# MFP_Schematic.net
KiCad netlist of a schematic drawn in EAGLE
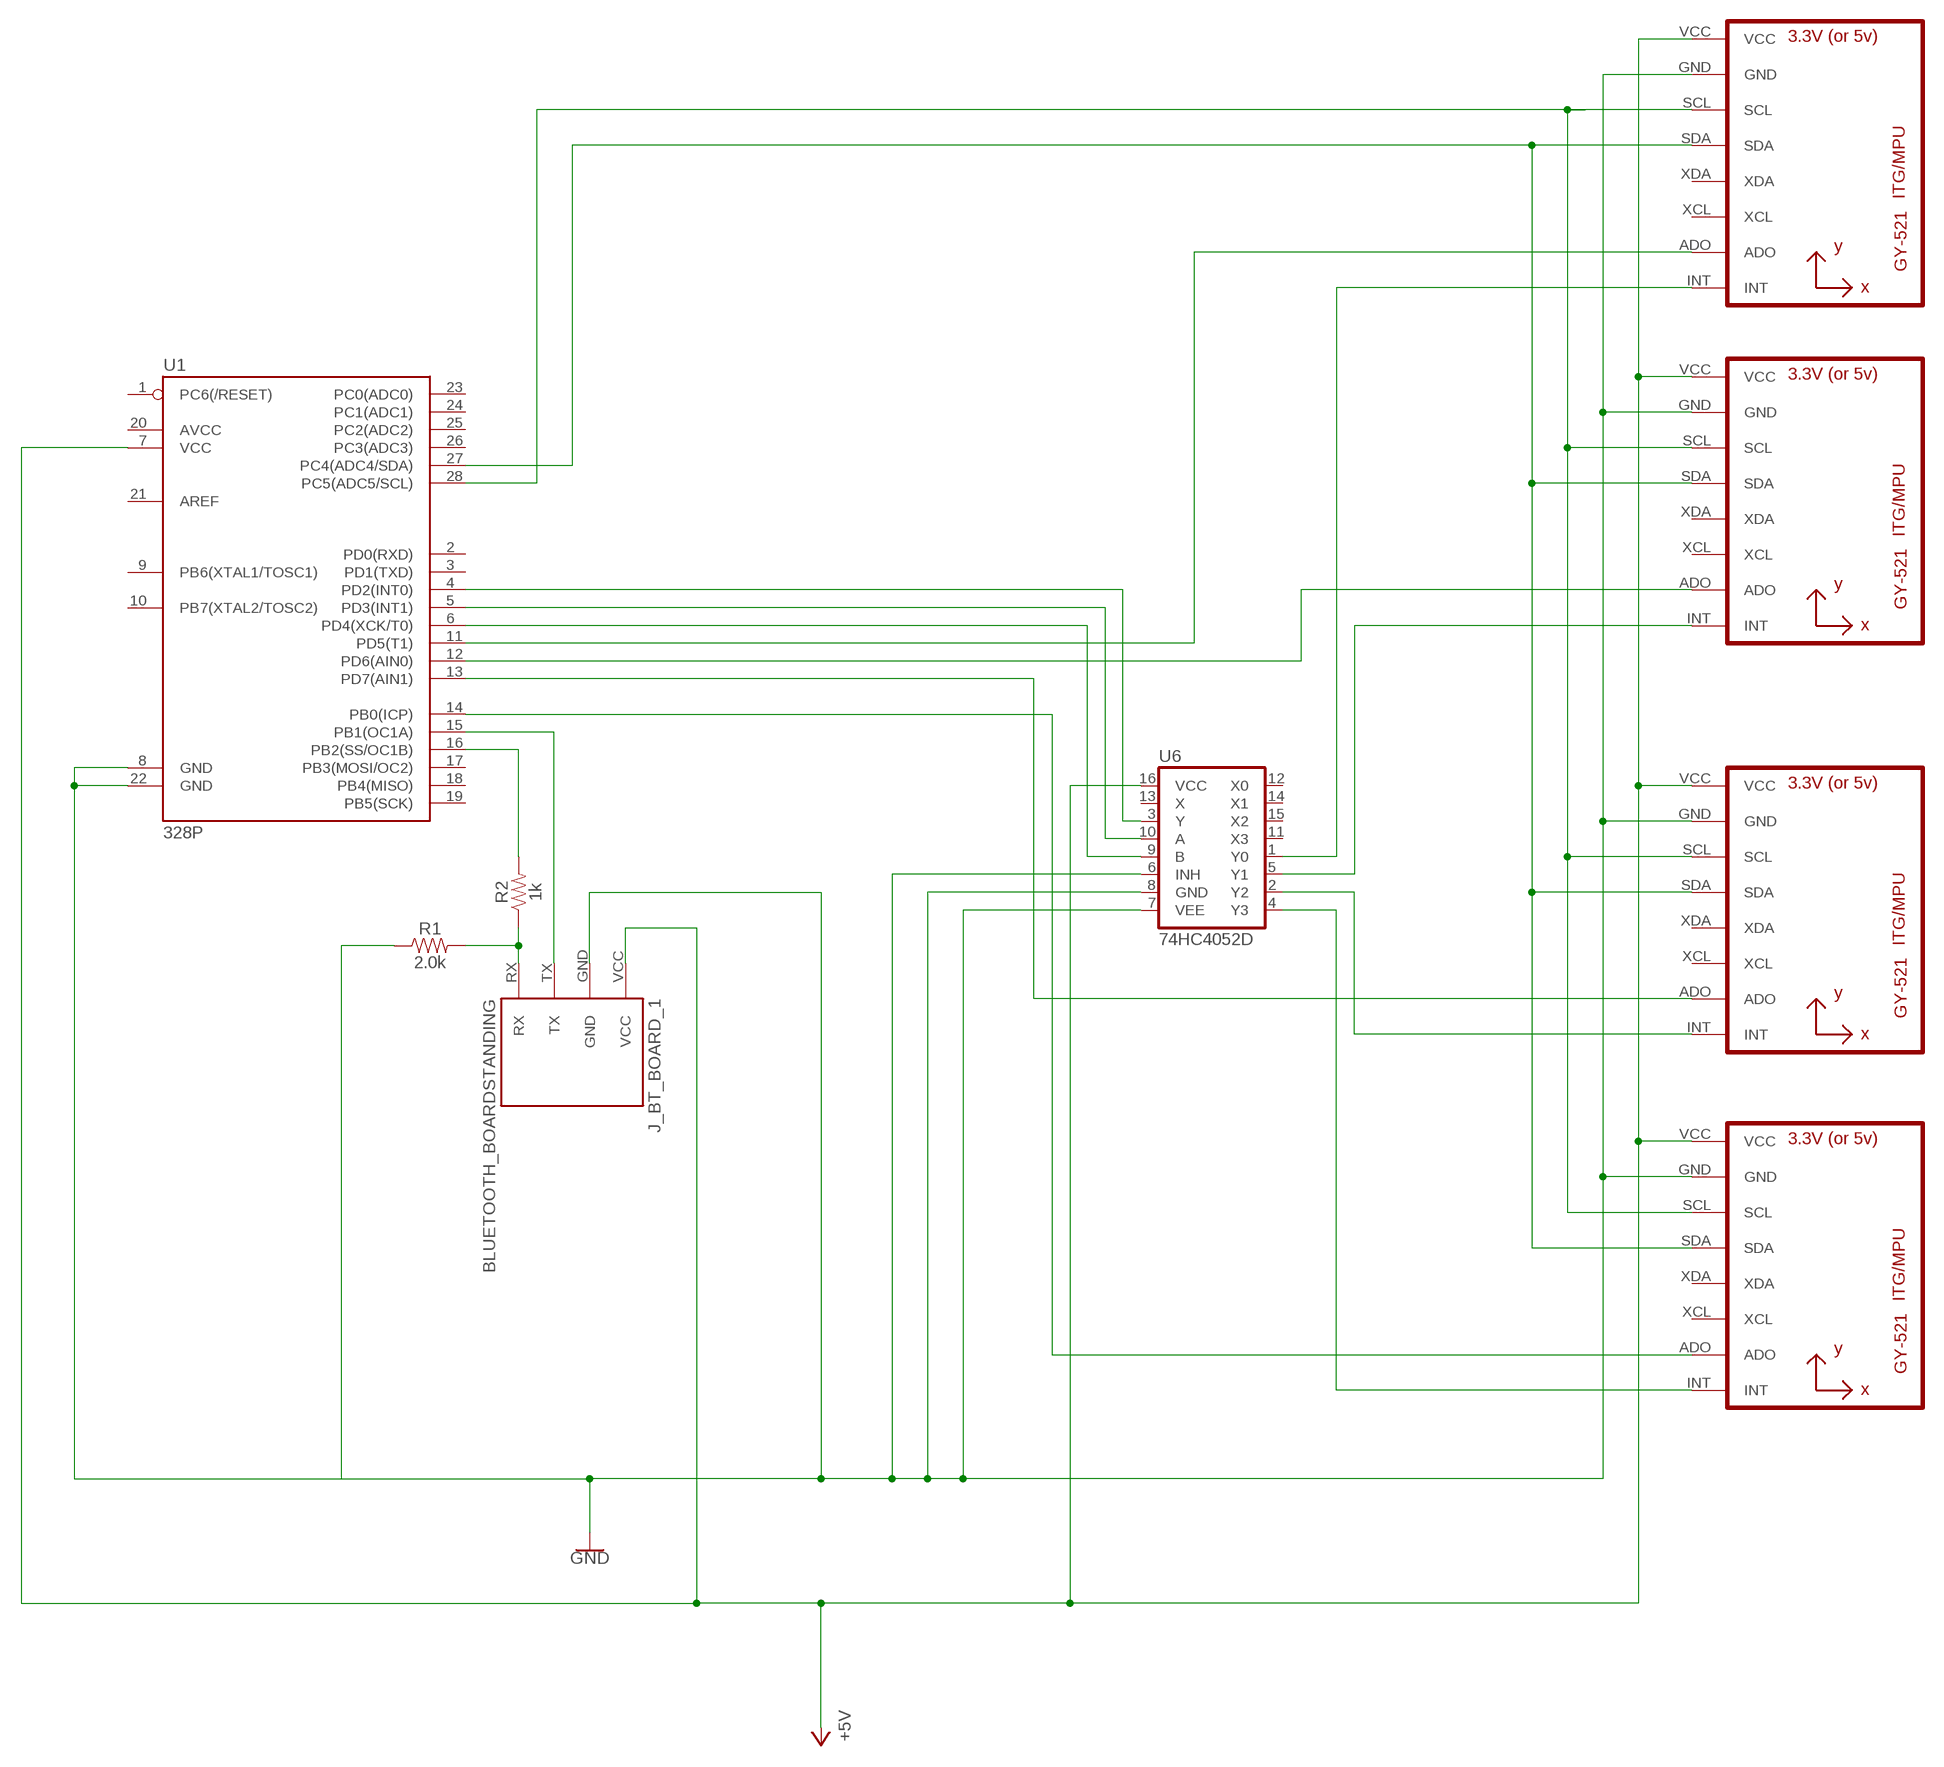
[diagram p0: schematic, sheet 1]

(export (version "E")
  (design (tool "Eeschema 10.0.6"))
  (components
    (comp (ref "J_BT_BOARD_1")
      (value "BLUETOOTH_BOARDSTANDING")
      (footprint "eagle-import:BT_BOARD_FOOTPRINT_STANDING")
      (libsource (lib "eagle-import") (part "BLUETOOTH_BOARDSTANDING"))
    )
    (comp (ref "R1")
      (value "2.0k")
      (footprint "eagle-import:0603")
      (libsource (lib "eagle-import") (part "2.0KOHM-0603-1/10W-5%"))
    )
    (comp (ref "R2")
      (value "1k")
      (footprint "eagle-import:0603")
      (libsource (lib "eagle-import") (part "1KOHM-0603-1/10W-1%"))
    )
    (comp (ref "U1")
      (value "328P")
      (footprint "eagle-import:DIP28")
      (libsource (lib "eagle-import") (part "ATMEGA328P_PDIP"))
    )
    (comp (ref "U2")
      (value "GY-521MPU6050")
      (footprint "eagle-import:GY-521")
      (libsource (lib "eagle-import") (part "GY-521MPU6050"))
    )
    (comp (ref "U3")
      (value "GY-521MPU6050")
      (footprint "eagle-import:GY-521")
      (libsource (lib "eagle-import") (part "GY-521MPU6050"))
    )
    (comp (ref "U4")
      (value "GY-521MPU6050")
      (footprint "eagle-import:GY-521")
      (libsource (lib "eagle-import") (part "GY-521MPU6050"))
    )
    (comp (ref "U5")
      (value "GY-521MPU6050")
      (footprint "eagle-import:GY-521")
      (libsource (lib "eagle-import") (part "GY-521MPU6050"))
    )
    (comp (ref "U6")
      (value "74HC4052D")
      (footprint "eagle-import:SO16")
      (libsource (lib "eagle-import") (part "744052DHC"))
    )
  )
  (nets
    (net (code "1") (name "+5V") (class "Default")
      (node (ref "J_BT_BOARD_1") (pin "VCC") (pinfunction "VCC_VCC") (pintype "bidirectional"))
      (node (ref "U1") (pin "7") (pinfunction "VCC_7") (pintype "bidirectional"))
      (node (ref "U2") (pin "VCC") (pinfunction "VCC_VCC") (pintype "bidirectional"))
      (node (ref "U3") (pin "VCC") (pinfunction "VCC_VCC") (pintype "bidirectional"))
      (node (ref "U4") (pin "VCC") (pinfunction "VCC_VCC") (pintype "bidirectional"))
      (node (ref "U5") (pin "VCC") (pinfunction "VCC_VCC") (pintype "bidirectional"))
      (node (ref "U6") (pin "16") (pinfunction "VCC_16") (pintype "power_in"))
    )
    (net (code "2") (name "GND") (class "Default")
      (node (ref "J_BT_BOARD_1") (pin "GND") (pinfunction "GND_GND") (pintype "bidirectional"))
      (node (ref "R1") (pin "1") (pinfunction "1_1") (pintype "passive"))
      (node (ref "U1") (pin "22") (pinfunction "GND_22") (pintype "bidirectional"))
      (node (ref "U1") (pin "8") (pinfunction "GND_8") (pintype "bidirectional"))
      (node (ref "U2") (pin "GND") (pinfunction "GND_GND") (pintype "bidirectional"))
      (node (ref "U3") (pin "GND") (pinfunction "GND_GND") (pintype "bidirectional"))
      (node (ref "U4") (pin "GND") (pinfunction "GND_GND") (pintype "bidirectional"))
      (node (ref "U5") (pin "GND") (pinfunction "GND_GND") (pintype "bidirectional"))
      (node (ref "U6") (pin "6") (pinfunction "INH_6") (pintype "input"))
      (node (ref "U6") (pin "7") (pinfunction "VEE_7") (pintype "power_in"))
      (node (ref "U6") (pin "8") (pinfunction "GND_8") (pintype "power_in"))
    )
    (net (code "3") (name "Net-(J_BT_BOARD_1-PadRX)") (class "Default")
      (node (ref "J_BT_BOARD_1") (pin "RX") (pinfunction "RX_RX") (pintype "bidirectional"))
      (node (ref "R1") (pin "2") (pinfunction "2_2") (pintype "passive"))
      (node (ref "R2") (pin "1") (pinfunction "1_1") (pintype "passive"))
    )
    (net (code "4") (name "Net-(U1-PB0(ICP))") (class "Default")
      (node (ref "U1") (pin "14") (pinfunction "PB0(ICP)_14") (pintype "bidirectional"))
      (node (ref "U5") (pin "ADO") (pinfunction "ADO_ADO") (pintype "bidirectional"))
    )
    (net (code "5") (name "Net-(U1-PB1(OC1A))") (class "Default")
      (node (ref "J_BT_BOARD_1") (pin "TX") (pinfunction "TX_TX") (pintype "bidirectional"))
      (node (ref "U1") (pin "15") (pinfunction "PB1(OC1A)_15") (pintype "bidirectional"))
    )
    (net (code "6") (name "Net-(U1-PB2(SS{slash}OC1B))") (class "Default")
      (node (ref "R2") (pin "2") (pinfunction "2_2") (pintype "passive"))
      (node (ref "U1") (pin "16") (pinfunction "PB2(SS/OC1B)_16") (pintype "bidirectional"))
    )
    (net (code "7") (name "Net-(U1-PC4(ADC4{slash}SDA))") (class "Default")
      (node (ref "U1") (pin "27") (pinfunction "PC4(ADC4/SDA)_27") (pintype "bidirectional"))
      (node (ref "U2") (pin "SDA") (pinfunction "SDA_SDA") (pintype "bidirectional"))
      (node (ref "U3") (pin "SDA") (pinfunction "SDA_SDA") (pintype "bidirectional"))
      (node (ref "U4") (pin "SDA") (pinfunction "SDA_SDA") (pintype "bidirectional"))
      (node (ref "U5") (pin "SDA") (pinfunction "SDA_SDA") (pintype "bidirectional"))
    )
    (net (code "8") (name "Net-(U1-PC5(ADC5{slash}SCL))") (class "Default")
      (node (ref "U1") (pin "28") (pinfunction "PC5(ADC5/SCL)_28") (pintype "bidirectional"))
      (node (ref "U2") (pin "SCL") (pinfunction "SCL_SCL") (pintype "bidirectional"))
      (node (ref "U3") (pin "SCL") (pinfunction "SCL_SCL") (pintype "bidirectional"))
      (node (ref "U4") (pin "SCL") (pinfunction "SCL_SCL") (pintype "bidirectional"))
      (node (ref "U5") (pin "SCL") (pinfunction "SCL_SCL") (pintype "bidirectional"))
    )
    (net (code "9") (name "Net-(U1-PD2(INT0))") (class "Default")
      (node (ref "U1") (pin "4") (pinfunction "PD2(INT0)_4") (pintype "bidirectional"))
      (node (ref "U6") (pin "3") (pinfunction "Y_3") (pintype "bidirectional"))
    )
    (net (code "10") (name "Net-(U1-PD3(INT1))") (class "Default")
      (node (ref "U1") (pin "5") (pinfunction "PD3(INT1)_5") (pintype "bidirectional"))
      (node (ref "U6") (pin "10") (pinfunction "A_10") (pintype "input"))
    )
    (net (code "11") (name "Net-(U1-PD4(XCK{slash}T0))") (class "Default")
      (node (ref "U1") (pin "6") (pinfunction "PD4(XCK/T0)_6") (pintype "bidirectional"))
      (node (ref "U6") (pin "9") (pinfunction "B_9") (pintype "input"))
    )
    (net (code "12") (name "Net-(U1-PD5(T1))") (class "Default")
      (node (ref "U1") (pin "11") (pinfunction "PD5(T1)_11") (pintype "bidirectional"))
      (node (ref "U4") (pin "ADO") (pinfunction "ADO_ADO") (pintype "bidirectional"))
    )
    (net (code "13") (name "Net-(U1-PD6(AIN0))") (class "Default")
      (node (ref "U1") (pin "12") (pinfunction "PD6(AIN0)_12") (pintype "bidirectional"))
      (node (ref "U2") (pin "ADO") (pinfunction "ADO_ADO") (pintype "bidirectional"))
    )
    (net (code "14") (name "Net-(U1-PD7(AIN1))") (class "Default")
      (node (ref "U1") (pin "13") (pinfunction "PD7(AIN1)_13") (pintype "bidirectional"))
      (node (ref "U3") (pin "ADO") (pinfunction "ADO_ADO") (pintype "bidirectional"))
    )
    (net (code "15") (name "Net-(U6-Y0)") (class "Default")
      (node (ref "U4") (pin "INT") (pinfunction "INT_INT") (pintype "bidirectional"))
      (node (ref "U6") (pin "1") (pinfunction "Y0_1") (pintype "bidirectional"))
    )
    (net (code "16") (name "Net-(U6-Y1)") (class "Default")
      (node (ref "U2") (pin "INT") (pinfunction "INT_INT") (pintype "bidirectional"))
      (node (ref "U6") (pin "5") (pinfunction "Y1_5") (pintype "bidirectional"))
    )
    (net (code "17") (name "Net-(U6-Y2)") (class "Default")
      (node (ref "U3") (pin "INT") (pinfunction "INT_INT") (pintype "bidirectional"))
      (node (ref "U6") (pin "2") (pinfunction "Y2_2") (pintype "bidirectional"))
    )
    (net (code "18") (name "Net-(U6-Y3)") (class "Default")
      (node (ref "U5") (pin "INT") (pinfunction "INT_INT") (pintype "bidirectional"))
      (node (ref "U6") (pin "4") (pinfunction "Y3_4") (pintype "bidirectional"))
    )
    (net (code "19") (name "unconnected-(U1-AREF-Pad21)") (class "Default")
      (node (ref "U1") (pin "21") (pinfunction "AREF_21") (pintype "bidirectional"))
    )
    (net (code "20") (name "unconnected-(U1-AVCC-Pad20)") (class "Default")
      (node (ref "U1") (pin "20") (pinfunction "AVCC_20") (pintype "bidirectional"))
    )
    (net (code "21") (name "unconnected-(U1-PB3(MOSI{slash}OC2)-Pad17)") (class "Default")
      (node (ref "U1") (pin "17") (pinfunction "PB3(MOSI/OC2)_17") (pintype "bidirectional"))
    )
    (net (code "22") (name "unconnected-(U1-PB4(MISO)-Pad18)") (class "Default")
      (node (ref "U1") (pin "18") (pinfunction "PB4(MISO)_18") (pintype "bidirectional"))
    )
    (net (code "23") (name "unconnected-(U1-PB5(SCK)-Pad19)") (class "Default")
      (node (ref "U1") (pin "19") (pinfunction "PB5(SCK)_19") (pintype "bidirectional"))
    )
    (net (code "24") (name "unconnected-(U1-PB6(XTAL1{slash}TOSC1)-Pad9)") (class "Default")
      (node (ref "U1") (pin "9") (pinfunction "PB6(XTAL1/TOSC1)_9") (pintype "bidirectional"))
    )
    (net (code "25") (name "unconnected-(U1-PB7(XTAL2{slash}TOSC2)-Pad10)") (class "Default")
      (node (ref "U1") (pin "10") (pinfunction "PB7(XTAL2/TOSC2)_10") (pintype "bidirectional"))
    )
    (net (code "26") (name "unconnected-(U1-PC0(ADC0)-Pad23)") (class "Default")
      (node (ref "U1") (pin "23") (pinfunction "PC0(ADC0)_23") (pintype "bidirectional"))
    )
    (net (code "27") (name "unconnected-(U1-PC1(ADC1)-Pad24)") (class "Default")
      (node (ref "U1") (pin "24") (pinfunction "PC1(ADC1)_24") (pintype "bidirectional"))
    )
    (net (code "28") (name "unconnected-(U1-PC2(ADC2)-Pad25)") (class "Default")
      (node (ref "U1") (pin "25") (pinfunction "PC2(ADC2)_25") (pintype "bidirectional"))
    )
    (net (code "29") (name "unconnected-(U1-PC3(ADC3)-Pad26)") (class "Default")
      (node (ref "U1") (pin "26") (pinfunction "PC3(ADC3)_26") (pintype "bidirectional"))
    )
    (net (code "30") (name "unconnected-(U1-PC6({slash}RESET)-Pad1)") (class "Default")
      (node (ref "U1") (pin "1") (pinfunction "PC6(/RESET)_1") (pintype "bidirectional"))
    )
    (net (code "31") (name "unconnected-(U1-PD0(RXD)-Pad2)") (class "Default")
      (node (ref "U1") (pin "2") (pinfunction "PD0(RXD)_2") (pintype "bidirectional"))
    )
    (net (code "32") (name "unconnected-(U1-PD1(TXD)-Pad3)") (class "Default")
      (node (ref "U1") (pin "3") (pinfunction "PD1(TXD)_3") (pintype "bidirectional"))
    )
    (net (code "33") (name "unconnected-(U2-PadXCL)") (class "Default")
      (node (ref "U2") (pin "XCL") (pinfunction "XCL_XCL") (pintype "bidirectional"))
    )
    (net (code "34") (name "unconnected-(U2-PadXDA)") (class "Default")
      (node (ref "U2") (pin "XDA") (pinfunction "XDA_XDA") (pintype "bidirectional"))
    )
    (net (code "35") (name "unconnected-(U3-PadXCL)") (class "Default")
      (node (ref "U3") (pin "XCL") (pinfunction "XCL_XCL") (pintype "bidirectional"))
    )
    (net (code "36") (name "unconnected-(U3-PadXDA)") (class "Default")
      (node (ref "U3") (pin "XDA") (pinfunction "XDA_XDA") (pintype "bidirectional"))
    )
    (net (code "37") (name "unconnected-(U4-PadXCL)") (class "Default")
      (node (ref "U4") (pin "XCL") (pinfunction "XCL_XCL") (pintype "bidirectional"))
    )
    (net (code "38") (name "unconnected-(U4-PadXDA)") (class "Default")
      (node (ref "U4") (pin "XDA") (pinfunction "XDA_XDA") (pintype "bidirectional"))
    )
    (net (code "39") (name "unconnected-(U5-PadXCL)") (class "Default")
      (node (ref "U5") (pin "XCL") (pinfunction "XCL_XCL") (pintype "bidirectional"))
    )
    (net (code "40") (name "unconnected-(U5-PadXDA)") (class "Default")
      (node (ref "U5") (pin "XDA") (pinfunction "XDA_XDA") (pintype "bidirectional"))
    )
    (net (code "41") (name "unconnected-(U6-X-Pad13)") (class "Default")
      (node (ref "U6") (pin "13") (pinfunction "X_13") (pintype "bidirectional"))
    )
    (net (code "42") (name "unconnected-(U6-X0-Pad12)") (class "Default")
      (node (ref "U6") (pin "12") (pinfunction "X0_12") (pintype "bidirectional"))
    )
    (net (code "43") (name "unconnected-(U6-X1-Pad14)") (class "Default")
      (node (ref "U6") (pin "14") (pinfunction "X1_14") (pintype "bidirectional"))
    )
    (net (code "44") (name "unconnected-(U6-X2-Pad15)") (class "Default")
      (node (ref "U6") (pin "15") (pinfunction "X2_15") (pintype "bidirectional"))
    )
    (net (code "45") (name "unconnected-(U6-X3-Pad11)") (class "Default")
      (node (ref "U6") (pin "11") (pinfunction "X3_11") (pintype "bidirectional"))
    )
  )
)
